# chip.net
KiCad netlist of a schematic drawn in EAGLE
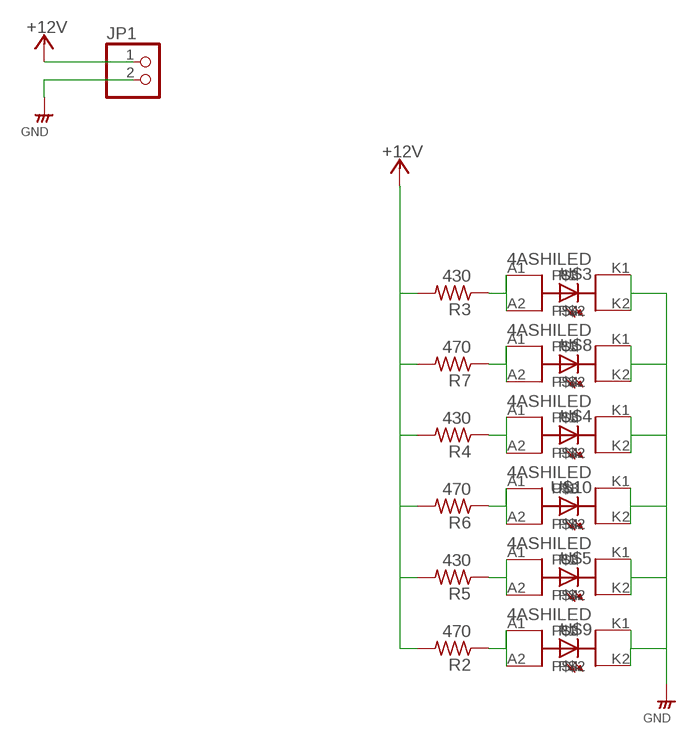
[diagram p0: schematic, sheet 1]

(export (version "E")
  (design (tool "Eeschema 10.0.6"))
  (components
    (comp (ref "JP1")
      (value "PINHD-1X2\"")
      (footprint "eagle-import:1_02")
      (libsource (lib "eagle-import") (part "PINHD-1X2{dblquote}"))
    )
    (comp (ref "R2")
      (value "470")
      (footprint "eagle-import:3216")
      (libsource (lib "eagle-import") (part "RESISTORS3216"))
    )
    (comp (ref "R3")
      (value "430")
      (footprint "eagle-import:3216")
      (libsource (lib "eagle-import") (part "RESISTORS3216"))
    )
    (comp (ref "R4")
      (value "430")
      (footprint "eagle-import:3216")
      (libsource (lib "eagle-import") (part "RESISTORS3216"))
    )
    (comp (ref "R5")
      (value "430")
      (footprint "eagle-import:3216")
      (libsource (lib "eagle-import") (part "RESISTORS3216"))
    )
    (comp (ref "R6")
      (value "470")
      (footprint "eagle-import:3216")
      (libsource (lib "eagle-import") (part "RESISTORS3216"))
    )
    (comp (ref "R7")
      (value "470")
      (footprint "eagle-import:3216")
      (libsource (lib "eagle-import") (part "RESISTORS3216"))
    )
    (comp (ref "U$3")
      (value "4ASHILED")
      (footprint "eagle-import:4AHILED-KAI")
      (libsource (lib "eagle-import") (part "4ASHILED"))
    )
    (comp (ref "U$4")
      (value "4ASHILED")
      (footprint "eagle-import:4AHILED-KAI")
      (libsource (lib "eagle-import") (part "4ASHILED"))
    )
    (comp (ref "U$5")
      (value "4ASHILED")
      (footprint "eagle-import:4AHILED-KAI")
      (libsource (lib "eagle-import") (part "4ASHILED"))
    )
    (comp (ref "U$8")
      (value "4ASHILED")
      (footprint "eagle-import:4AHILED-KAI")
      (libsource (lib "eagle-import") (part "4ASHILED"))
    )
    (comp (ref "U$9")
      (value "4ASHILED")
      (footprint "eagle-import:4AHILED-KAI")
      (libsource (lib "eagle-import") (part "4ASHILED"))
    )
    (comp (ref "U$10")
      (value "4ASHILED")
      (footprint "eagle-import:4AHILED-KAI")
      (libsource (lib "eagle-import") (part "4ASHILED"))
    )
  )
  (nets
    (net (code "1") (name "+12V") (class "Default")
      (node (ref "JP1") (pin "1") (pinfunction "1_1") (pintype "passive"))
      (node (ref "R2") (pin "2") (pinfunction "2_2") (pintype "passive"))
      (node (ref "R3") (pin "2") (pinfunction "2_2") (pintype "passive"))
      (node (ref "R4") (pin "2") (pinfunction "2_2") (pintype "passive"))
      (node (ref "R5") (pin "2") (pinfunction "2_2") (pintype "passive"))
      (node (ref "R6") (pin "2") (pinfunction "2_2") (pintype "passive"))
      (node (ref "R7") (pin "2") (pinfunction "2_2") (pintype "passive"))
    )
    (net (code "2") (name "GND") (class "Default")
      (node (ref "JP1") (pin "2") (pinfunction "2_2") (pintype "passive"))
      (node (ref "U$10") (pin "K1") (pinfunction "P$3_K1") (pintype "bidirectional"))
      (node (ref "U$10") (pin "K2") (pinfunction "P$4_K2") (pintype "bidirectional"))
      (node (ref "U$3") (pin "K1") (pinfunction "P$3_K1") (pintype "bidirectional"))
      (node (ref "U$3") (pin "K2") (pinfunction "P$4_K2") (pintype "bidirectional"))
      (node (ref "U$4") (pin "K1") (pinfunction "P$3_K1") (pintype "bidirectional"))
      (node (ref "U$4") (pin "K2") (pinfunction "P$4_K2") (pintype "bidirectional"))
      (node (ref "U$5") (pin "K1") (pinfunction "P$3_K1") (pintype "bidirectional"))
      (node (ref "U$5") (pin "K2") (pinfunction "P$4_K2") (pintype "bidirectional"))
      (node (ref "U$8") (pin "K1") (pinfunction "P$3_K1") (pintype "bidirectional"))
      (node (ref "U$8") (pin "K2") (pinfunction "P$4_K2") (pintype "bidirectional"))
      (node (ref "U$9") (pin "K1") (pinfunction "P$3_K1") (pintype "bidirectional"))
      (node (ref "U$9") (pin "K2") (pinfunction "P$4_K2") (pintype "bidirectional"))
    )
    (net (code "3") (name "Net-(U$3-P$2)") (class "Default")
      (node (ref "R3") (pin "1") (pinfunction "1_1") (pintype "passive"))
      (node (ref "U$3") (pin "A1") (pinfunction "P1_A1") (pintype "bidirectional"))
      (node (ref "U$3") (pin "A2") (pinfunction "P$2_A2") (pintype "bidirectional"))
    )
    (net (code "4") (name "Net-(U$4-P$2)") (class "Default")
      (node (ref "R4") (pin "1") (pinfunction "1_1") (pintype "passive"))
      (node (ref "U$4") (pin "A1") (pinfunction "P1_A1") (pintype "bidirectional"))
      (node (ref "U$4") (pin "A2") (pinfunction "P$2_A2") (pintype "bidirectional"))
    )
    (net (code "5") (name "Net-(U$5-P$2)") (class "Default")
      (node (ref "R5") (pin "1") (pinfunction "1_1") (pintype "passive"))
      (node (ref "U$5") (pin "A1") (pinfunction "P1_A1") (pintype "bidirectional"))
      (node (ref "U$5") (pin "A2") (pinfunction "P$2_A2") (pintype "bidirectional"))
    )
    (net (code "6") (name "Net-(U$8-P$2)") (class "Default")
      (node (ref "R7") (pin "1") (pinfunction "1_1") (pintype "passive"))
      (node (ref "U$8") (pin "A1") (pinfunction "P1_A1") (pintype "bidirectional"))
      (node (ref "U$8") (pin "A2") (pinfunction "P$2_A2") (pintype "bidirectional"))
    )
    (net (code "7") (name "Net-(U$9-P$2)") (class "Default")
      (node (ref "R2") (pin "1") (pinfunction "1_1") (pintype "passive"))
      (node (ref "U$9") (pin "A1") (pinfunction "P1_A1") (pintype "bidirectional"))
      (node (ref "U$9") (pin "A2") (pinfunction "P$2_A2") (pintype "bidirectional"))
    )
    (net (code "8") (name "Net-(U$10-P$2)") (class "Default")
      (node (ref "R6") (pin "1") (pinfunction "1_1") (pintype "passive"))
      (node (ref "U$10") (pin "A1") (pinfunction "P1_A1") (pintype "bidirectional"))
      (node (ref "U$10") (pin "A2") (pinfunction "P$2_A2") (pintype "bidirectional"))
    )
  )
)
